# CW340_USERIO_debug.net
KiCad netlist of a schematic drawn in Altium Designer
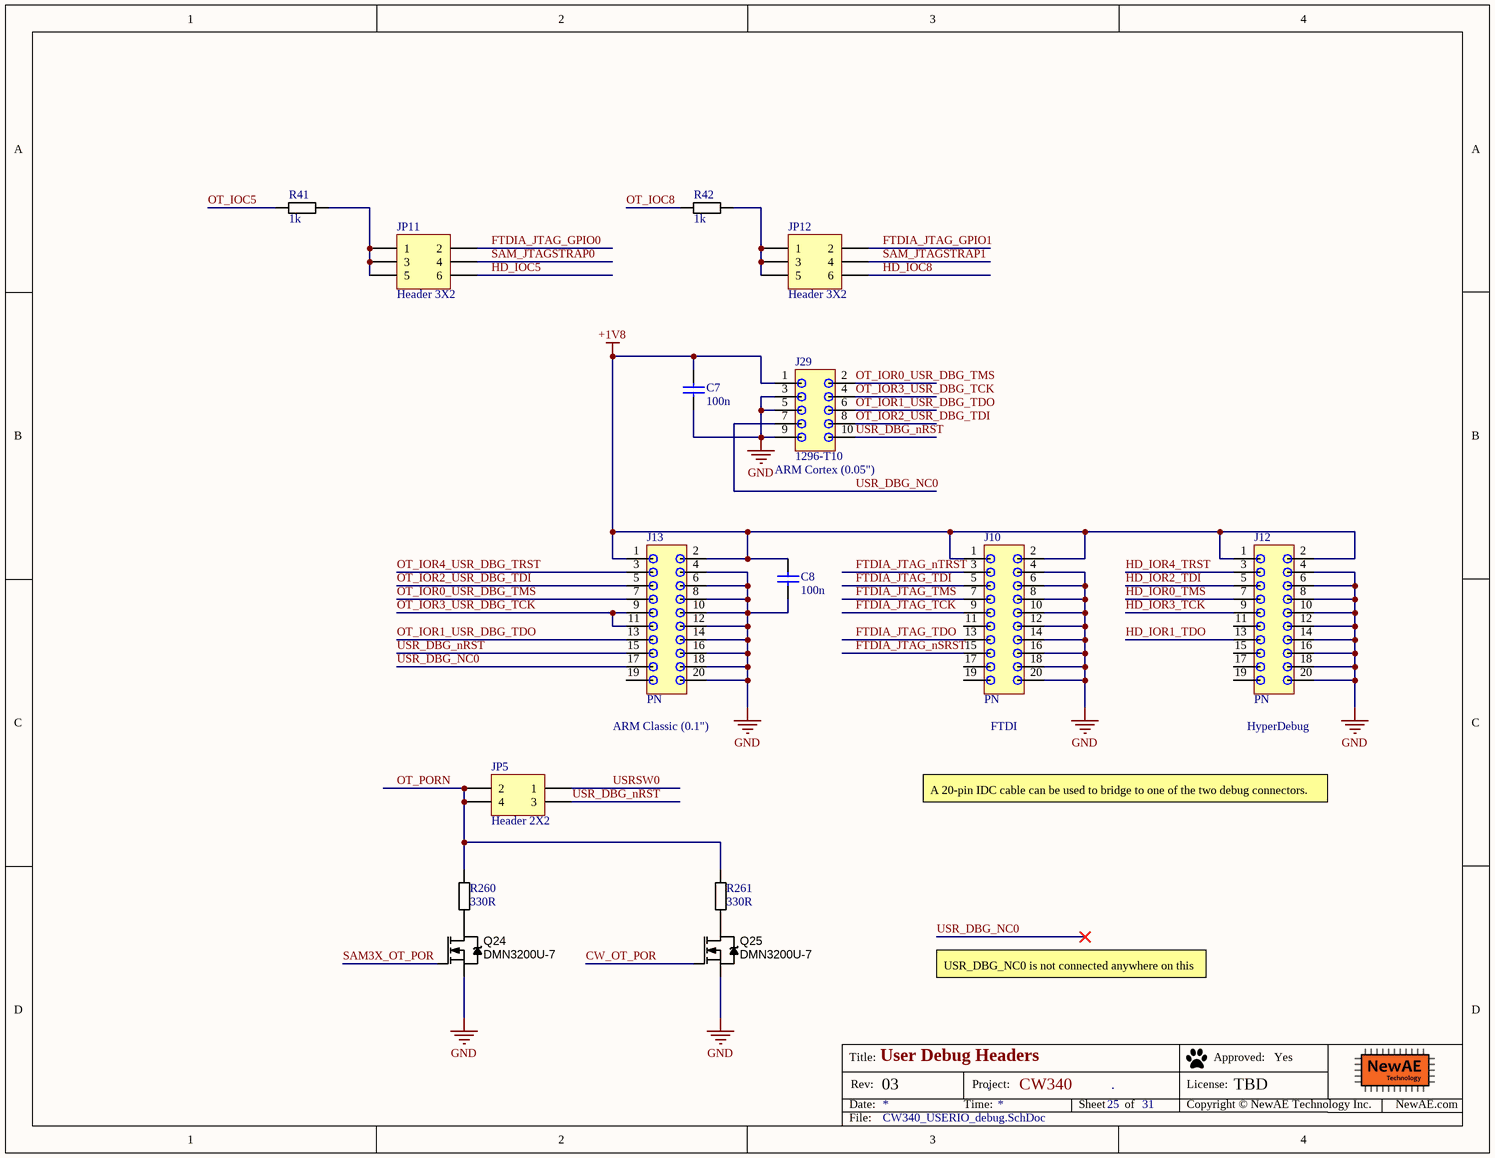
[diagram p0: CW340_USERIO_debug.SchDoc]

(export (version "E")
  (design (tool "Eeschema 10.0.6"))
  (components
    (comp (ref "C7")
      (value "100n")
      (footprint "CAPC0603_M")
      (description "100n, 0603")
      (fields (field (name "PART NUMBER") "CCHIP-100n-0603"))
      (libsource (lib "NewAE_AltiumLib") (part "CAP"))
    )
    (comp (ref "C8")
      (value "100n")
      (footprint "CAPC0603_M")
      (description "100n, 0603")
      (fields (field (name "PART NUMBER") "CCHIP-100n-0603"))
      (libsource (lib "NewAE_AltiumLib") (part "CAP"))
    )
    (comp (ref "J10")
      (value "PN")
      (footprint "CONN_10x2_SHROUDED_2.54mm")
      (description "Header, 2-Row, 20-pin, 0.1\"")
      (fields (field (name "PART NUMBER") "CONN20_2ROW"))
      (libsource (lib "NewAE_AltiumLib") (part "CON20_2ROW"))
    )
    (comp (ref "J12")
      (value "PN")
      (footprint "CONN_10x2_SHROUDED_2.54mm")
      (description "Header, 2-Row, 20-pin, 0.1\"")
      (fields (field (name "PART NUMBER") "CONN20_2ROW"))
      (libsource (lib "NewAE_AltiumLib") (part "CON20_2ROW"))
    )
    (comp (ref "J13")
      (value "PN")
      (footprint "CONN_10x2_SHROUDED_2.54mm")
      (description "Header, 2-Row, 20-pin, 0.1\"")
      (fields (field (name "PART NUMBER") "CONN20_2ROW"))
      (libsource (lib "NewAE_AltiumLib") (part "CON20_2ROW"))
    )
    (comp (ref "J29")
      (value "1296-T10")
      (footprint "1296-T10")
      (description "Header, 10-pin, SMD, 0.05\"")
      (libsource (lib "NewAE_AltiumLib") (part "CON10_2ROW"))
    )
    (comp (ref "JP5")
      (value "Header 2X2")
      (footprint "HDR2X2")
      (description "Header, 2-Pin, Dual row")
      (fields (field (name "PUBLISHER") "Altium Limited"))
      (libsource (lib "Miscellaneous Connectors") (part "Header 2X2"))
    )
    (comp (ref "JP11")
      (value "Header 3X2")
      (footprint "HDR2X3")
      (description "Header, 3-Pin, Dual row")
      (fields (field (name "PUBLISHER") "Altium Limited"))
      (libsource (lib "Miscellaneous Connectors") (part "Header 3X2"))
    )
    (comp (ref "JP12")
      (value "Header 3X2")
      (footprint "HDR2X3")
      (description "Header, 3-Pin, Dual row")
      (fields (field (name "PUBLISHER") "Altium Limited"))
      (libsource (lib "Miscellaneous Connectors") (part "Header 3X2"))
    )
    (comp (ref "Q24")
      (value "DMN3200U-7")
      (footprint "SOT95P245X110-3M")
      (description "MOSFET N-CH 30V 2.2A SOT23-3")
      (libsource (lib "NewAE_AltiumLib") (part "MOSFET_N_GSD"))
    )
    (comp (ref "Q25")
      (value "DMN3200U-7")
      (footprint "SOT95P245X110-3M")
      (description "MOSFET N-CH 30V 2.2A SOT23-3")
      (libsource (lib "NewAE_AltiumLib") (part "MOSFET_N_GSD"))
    )
    (comp (ref "R41")
      (value "1k")
      (footprint "RESC1608X55N")
      (description "1k res, 0603, 1%, 1/10W")
      (fields (field (name "PART NUMBER") "RCHIP-1K-0603") (field (name "TOLERANCE") "1%"))
      (libsource (lib "NewAE_AltiumLib") (part "RES-EU"))
    )
    (comp (ref "R42")
      (value "1k")
      (footprint "RESC1608X55N")
      (description "1k res, 0603, 1%, 1/10W")
      (fields (field (name "PART NUMBER") "RCHIP-1K-0603") (field (name "TOLERANCE") "1%"))
      (libsource (lib "NewAE_AltiumLib") (part "RES-EU"))
    )
    (comp (ref "R260")
      (value "330R")
      (footprint "RESC1608X55N")
      (description "330R res, 0603, 1%, 1/10W")
      (fields (field (name "PART NUMBER") "RCHIP-330R-0603") (field (name "TOLERANCE") "1%"))
      (libsource (lib "") (part "RES-EU_1"))
    )
    (comp (ref "R261")
      (value "330R")
      (footprint "RESC1608X55N")
      (description "330R res, 0603, 1%, 1/10W")
      (fields (field (name "PART NUMBER") "RCHIP-330R-0603") (field (name "TOLERANCE") "1%"))
      (libsource (lib "") (part "RES-EU_1"))
    )
  )
  (nets
    (net (code "1") (name "+1V8") (class "Default")
      (node (ref "C7") (pin "2") (pinfunction "2_2") (pintype "passive"))
      (node (ref "C8") (pin "2") (pinfunction "2_2") (pintype "passive"))
      (node (ref "J10") (pin "1") (pinfunction "1_1") (pintype "passive"))
      (node (ref "J10") (pin "2") (pinfunction "2_2") (pintype "passive"))
      (node (ref "J12") (pin "1") (pinfunction "1_1") (pintype "passive"))
      (node (ref "J12") (pin "2") (pinfunction "2_2") (pintype "passive"))
      (node (ref "J13") (pin "1") (pinfunction "1_1") (pintype "passive"))
      (node (ref "J13") (pin "2") (pinfunction "2_2") (pintype "passive"))
      (node (ref "J29") (pin "1") (pinfunction "1_1") (pintype "passive"))
    )
    (net (code "2") (name "/CW_OT_POR") (class "Default")
      (node (ref "Q25") (pin "1") (pinfunction "G_1") (pintype "passive"))
    )
    (net (code "3") (name "/FTDIA_JTAG_GPIO0") (class "Default")
      (node (ref "JP11") (pin "2") (pinfunction "2_2") (pintype "passive"))
    )
    (net (code "4") (name "/FTDIA_JTAG_GPIO1") (class "Default")
      (node (ref "JP12") (pin "2") (pinfunction "2_2") (pintype "passive"))
    )
    (net (code "5") (name "/FTDIA_JTAG_TCK") (class "Default")
      (node (ref "J10") (pin "9") (pinfunction "9_9") (pintype "passive"))
    )
    (net (code "6") (name "/FTDIA_JTAG_TDI") (class "Default")
      (node (ref "J10") (pin "5") (pinfunction "5_5") (pintype "passive"))
    )
    (net (code "7") (name "/FTDIA_JTAG_TDO") (class "Default")
      (node (ref "J10") (pin "13") (pinfunction "9_13") (pintype "passive"))
    )
    (net (code "8") (name "/FTDIA_JTAG_TMS") (class "Default")
      (node (ref "J10") (pin "7") (pinfunction "7_7") (pintype "passive"))
    )
    (net (code "9") (name "/FTDIA_JTAG_nSRST") (class "Default")
      (node (ref "J10") (pin "15") (pinfunction "9_15") (pintype "passive"))
    )
    (net (code "10") (name "/FTDIA_JTAG_nTRST") (class "Default")
      (node (ref "J10") (pin "3") (pinfunction "3_3") (pintype "passive"))
    )
    (net (code "11") (name "/HD_IOC5") (class "Default")
      (node (ref "JP11") (pin "6") (pinfunction "6_6") (pintype "passive"))
    )
    (net (code "12") (name "/HD_IOC8") (class "Default")
      (node (ref "JP12") (pin "6") (pinfunction "6_6") (pintype "passive"))
    )
    (net (code "13") (name "/HD_IOR0_TMS") (class "Default")
      (node (ref "J12") (pin "7") (pinfunction "7_7") (pintype "passive"))
    )
    (net (code "14") (name "/HD_IOR1_TDO") (class "Default")
      (node (ref "J12") (pin "13") (pinfunction "9_13") (pintype "passive"))
    )
    (net (code "15") (name "/HD_IOR2_TDI") (class "Default")
      (node (ref "J12") (pin "5") (pinfunction "5_5") (pintype "passive"))
    )
    (net (code "16") (name "/HD_IOR3_TCK") (class "Default")
      (node (ref "J12") (pin "9") (pinfunction "9_9") (pintype "passive"))
    )
    (net (code "17") (name "/HD_IOR4_TRST") (class "Default")
      (node (ref "J12") (pin "3") (pinfunction "3_3") (pintype "passive"))
    )
    (net (code "18") (name "/OT_IOC5") (class "Default")
      (node (ref "R41") (pin "1") (pinfunction "1_1") (pintype "passive"))
    )
    (net (code "19") (name "/OT_IOC8") (class "Default")
      (node (ref "R42") (pin "1") (pinfunction "1_1") (pintype "passive"))
    )
    (net (code "20") (name "/OT_IOR0_USR_DBG_TMS") (class "Default")
      (node (ref "J13") (pin "7") (pinfunction "7_7") (pintype "passive"))
      (node (ref "J29") (pin "2") (pinfunction "2_2") (pintype "passive"))
    )
    (net (code "21") (name "/OT_IOR1_USR_DBG_TDO") (class "Default")
      (node (ref "J13") (pin "13") (pinfunction "9_13") (pintype "passive"))
      (node (ref "J29") (pin "6") (pinfunction "6_6") (pintype "passive"))
    )
    (net (code "22") (name "/OT_IOR2_USR_DBG_TDI") (class "Default")
      (node (ref "J13") (pin "5") (pinfunction "5_5") (pintype "passive"))
      (node (ref "J29") (pin "8") (pinfunction "8_8") (pintype "passive"))
    )
    (net (code "23") (name "/OT_IOR3_USR_DBG_TCK") (class "Default")
      (node (ref "J13") (pin "11") (pinfunction "9_11") (pintype "passive"))
      (node (ref "J13") (pin "9") (pinfunction "9_9") (pintype "passive"))
      (node (ref "J29") (pin "4") (pinfunction "4_4") (pintype "passive"))
    )
    (net (code "24") (name "/OT_IOR4_USR_DBG_TRST") (class "Default")
      (node (ref "J13") (pin "3") (pinfunction "3_3") (pintype "passive"))
    )
    (net (code "25") (name "/OT_PORN") (class "Default")
      (node (ref "JP5") (pin "2") (pinfunction "2_2") (pintype "passive"))
      (node (ref "JP5") (pin "4") (pinfunction "4_4") (pintype "passive"))
      (node (ref "R260") (pin "2") (pinfunction "2_2") (pintype "passive"))
      (node (ref "R261") (pin "2") (pinfunction "2_2") (pintype "passive"))
    )
    (net (code "26") (name "/SAM3X_OT_POR") (class "Default")
      (node (ref "Q24") (pin "1") (pinfunction "G_1") (pintype "passive"))
    )
    (net (code "27") (name "/SAM_JTAGSTRAP0") (class "Default")
      (node (ref "JP11") (pin "4") (pinfunction "4_4") (pintype "passive"))
    )
    (net (code "28") (name "/SAM_JTAGSTRAP1") (class "Default")
      (node (ref "JP12") (pin "4") (pinfunction "4_4") (pintype "passive"))
    )
    (net (code "29") (name "/USRSW0") (class "Default")
      (node (ref "JP5") (pin "1") (pinfunction "1_1") (pintype "passive"))
    )
    (net (code "30") (name "/USR_DBG_NC0") (class "Default")
      (node (ref "J13") (pin "17") (pinfunction "9_17") (pintype "passive"))
      (node (ref "J29") (pin "7") (pinfunction "7_7") (pintype "passive"))
    )
    (net (code "31") (name "/USR_DBG_nRST") (class "Default")
      (node (ref "J13") (pin "15") (pinfunction "9_15") (pintype "passive"))
      (node (ref "J29") (pin "10") (pinfunction "10_10") (pintype "passive"))
      (node (ref "JP5") (pin "3") (pinfunction "3_3") (pintype "passive"))
    )
    (net (code "32") (name "GND") (class "Default")
      (node (ref "C7") (pin "1") (pinfunction "1_1") (pintype "passive"))
      (node (ref "C8") (pin "1") (pinfunction "1_1") (pintype "passive"))
      (node (ref "J10") (pin "10") (pinfunction "10_10") (pintype "passive"))
      (node (ref "J10") (pin "12") (pinfunction "10_12") (pintype "passive"))
      (node (ref "J10") (pin "14") (pinfunction "10_14") (pintype "passive"))
      (node (ref "J10") (pin "16") (pinfunction "10_16") (pintype "passive"))
      (node (ref "J10") (pin "18") (pinfunction "10_18") (pintype "passive"))
      (node (ref "J10") (pin "20") (pinfunction "10_20") (pintype "passive"))
      (node (ref "J10") (pin "4") (pinfunction "4_4") (pintype "passive"))
      (node (ref "J10") (pin "6") (pinfunction "6_6") (pintype "passive"))
      (node (ref "J10") (pin "8") (pinfunction "8_8") (pintype "passive"))
      (node (ref "J12") (pin "10") (pinfunction "10_10") (pintype "passive"))
      (node (ref "J12") (pin "12") (pinfunction "10_12") (pintype "passive"))
      (node (ref "J12") (pin "14") (pinfunction "10_14") (pintype "passive"))
      (node (ref "J12") (pin "16") (pinfunction "10_16") (pintype "passive"))
      (node (ref "J12") (pin "18") (pinfunction "10_18") (pintype "passive"))
      (node (ref "J12") (pin "20") (pinfunction "10_20") (pintype "passive"))
      (node (ref "J12") (pin "4") (pinfunction "4_4") (pintype "passive"))
      (node (ref "J12") (pin "6") (pinfunction "6_6") (pintype "passive"))
      (node (ref "J12") (pin "8") (pinfunction "8_8") (pintype "passive"))
      (node (ref "J13") (pin "10") (pinfunction "10_10") (pintype "passive"))
      (node (ref "J13") (pin "12") (pinfunction "10_12") (pintype "passive"))
      (node (ref "J13") (pin "14") (pinfunction "10_14") (pintype "passive"))
      (node (ref "J13") (pin "16") (pinfunction "10_16") (pintype "passive"))
      (node (ref "J13") (pin "18") (pinfunction "10_18") (pintype "passive"))
      (node (ref "J13") (pin "20") (pinfunction "10_20") (pintype "passive"))
      (node (ref "J13") (pin "4") (pinfunction "4_4") (pintype "passive"))
      (node (ref "J13") (pin "6") (pinfunction "6_6") (pintype "passive"))
      (node (ref "J13") (pin "8") (pinfunction "8_8") (pintype "passive"))
      (node (ref "J29") (pin "3") (pinfunction "3_3") (pintype "passive"))
      (node (ref "J29") (pin "5") (pinfunction "5_5") (pintype "passive"))
      (node (ref "J29") (pin "9") (pinfunction "9_9") (pintype "passive"))
      (node (ref "Q24") (pin "2") (pinfunction "S_2") (pintype "passive"))
      (node (ref "Q25") (pin "2") (pinfunction "S_2") (pintype "passive"))
    )
    (net (code "33") (name "Net-(JP11-Pad1)") (class "Default")
      (node (ref "JP11") (pin "1") (pinfunction "1_1") (pintype "passive"))
      (node (ref "JP11") (pin "3") (pinfunction "3_3") (pintype "passive"))
      (node (ref "JP11") (pin "5") (pinfunction "5_5") (pintype "passive"))
      (node (ref "R41") (pin "2") (pinfunction "2_2") (pintype "passive"))
    )
    (net (code "34") (name "Net-(JP12-Pad1)") (class "Default")
      (node (ref "JP12") (pin "1") (pinfunction "1_1") (pintype "passive"))
      (node (ref "JP12") (pin "3") (pinfunction "3_3") (pintype "passive"))
      (node (ref "JP12") (pin "5") (pinfunction "5_5") (pintype "passive"))
      (node (ref "R42") (pin "2") (pinfunction "2_2") (pintype "passive"))
    )
    (net (code "35") (name "Net-(Q24-D)") (class "Default")
      (node (ref "Q24") (pin "3") (pinfunction "D_3") (pintype "passive"))
      (node (ref "R260") (pin "1") (pinfunction "1_1") (pintype "passive"))
    )
    (net (code "36") (name "Net-(Q25-D)") (class "Default")
      (node (ref "Q25") (pin "3") (pinfunction "D_3") (pintype "passive"))
      (node (ref "R261") (pin "1") (pinfunction "1_1") (pintype "passive"))
    )
    (net (code "37") (name "unconnected-(J10-9-Pad11)") (class "Default")
      (node (ref "J10") (pin "11") (pinfunction "9_11") (pintype "passive"))
    )
    (net (code "38") (name "unconnected-(J10-9-Pad17)") (class "Default")
      (node (ref "J10") (pin "17") (pinfunction "9_17") (pintype "passive"))
    )
    (net (code "39") (name "unconnected-(J10-9-Pad19)") (class "Default")
      (node (ref "J10") (pin "19") (pinfunction "9_19") (pintype "passive"))
    )
    (net (code "40") (name "unconnected-(J12-9-Pad11)") (class "Default")
      (node (ref "J12") (pin "11") (pinfunction "9_11") (pintype "passive"))
    )
    (net (code "41") (name "unconnected-(J12-9-Pad15)") (class "Default")
      (node (ref "J12") (pin "15") (pinfunction "9_15") (pintype "passive"))
    )
    (net (code "42") (name "unconnected-(J12-9-Pad17)") (class "Default")
      (node (ref "J12") (pin "17") (pinfunction "9_17") (pintype "passive"))
    )
    (net (code "43") (name "unconnected-(J12-9-Pad19)") (class "Default")
      (node (ref "J12") (pin "19") (pinfunction "9_19") (pintype "passive"))
    )
    (net (code "44") (name "unconnected-(J13-9-Pad19)") (class "Default")
      (node (ref "J13") (pin "19") (pinfunction "9_19") (pintype "passive"))
    )
  )
)
